# uStar_v1.net
KiCad netlist of a schematic drawn in EAGLE
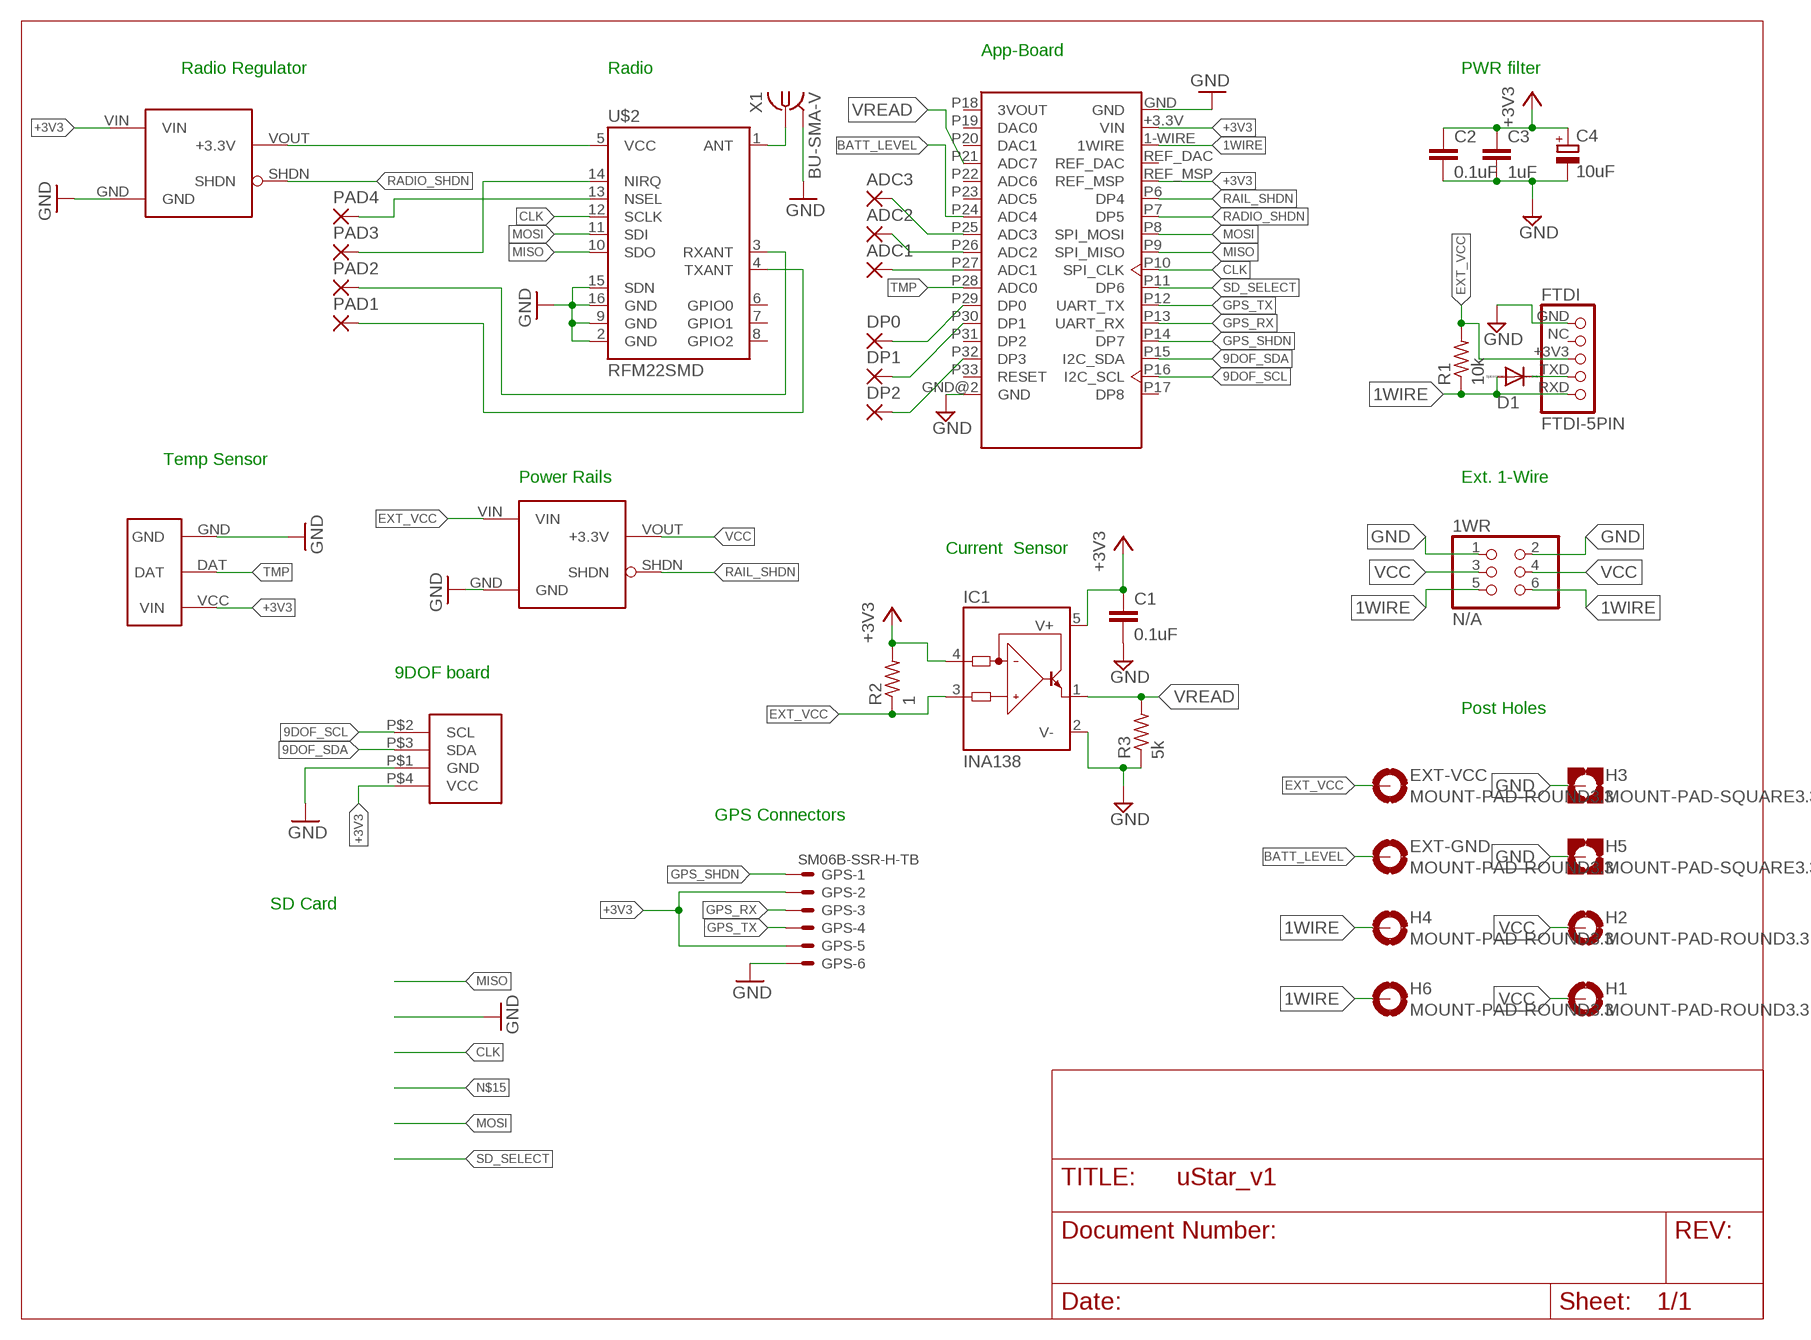
[diagram p0: schematic, sheet 1]

(export (version "E")
  (design (tool "Eeschema 10.0.6"))
  (components
    (comp (ref "1WR")
      (value "N/A")
      (footprint "eagle-import:2X03")
      (libsource (lib "eagle-import") (part "PINHD-2X3"))
    )
    (comp (ref "ADC1")
      (value "1,6/0,9")
      (footprint "eagle-import:1,6_0,9")
      (libsource (lib "eagle-import") (part "1,6/0,9"))
    )
    (comp (ref "ADC2")
      (value "1,6/0,9")
      (footprint "eagle-import:1,6_0,9")
      (libsource (lib "eagle-import") (part "1,6/0,9"))
    )
    (comp (ref "ADC3")
      (value "1,6/0,9")
      (footprint "eagle-import:1,6_0,9")
      (libsource (lib "eagle-import") (part "1,6/0,9"))
    )
    (comp (ref "C1")
      (value "0.1uF")
      (footprint "eagle-import:C0805")
      (libsource (lib "eagle-import") (part "C-EUC0805"))
    )
    (comp (ref "C2")
      (value "0.1uF")
      (footprint "eagle-import:C0603")
      (libsource (lib "eagle-import") (part "C-EUC0603"))
    )
    (comp (ref "C3")
      (value "1uF")
      (footprint "eagle-import:C0603")
      (libsource (lib "eagle-import") (part "C-EUC0603"))
    )
    (comp (ref "C4")
      (value "10uF")
      (footprint "eagle-import:SMC_B")
      (libsource (lib "eagle-import") (part "CPOL-EUSMCB"))
    )
    (comp (ref "D1")
      (value "1N4148DO35-7")
      (footprint "eagle-import:DO35-7")
      (libsource (lib "eagle-import") (part "1N4148DO35-7"))
    )
    (comp (ref "DP0")
      (value "1,6/0,9")
      (footprint "eagle-import:1,6_0,9")
      (libsource (lib "eagle-import") (part "1,6/0,9"))
    )
    (comp (ref "DP1")
      (value "1,6/0,9")
      (footprint "eagle-import:1,6_0,9")
      (libsource (lib "eagle-import") (part "1,6/0,9"))
    )
    (comp (ref "DP2")
      (value "1,6/0,9")
      (footprint "eagle-import:1,6_0,9")
      (libsource (lib "eagle-import") (part "1,6/0,9"))
    )
    (comp (ref "EXT-GND")
      (value "MOUNT-PAD-ROUND3.3")
      (footprint "eagle-import:3,3-PAD")
      (libsource (lib "eagle-import") (part "MOUNT-PAD-ROUND3.3"))
    )
    (comp (ref "EXT-VCC")
      (value "MOUNT-PAD-ROUND3.3")
      (footprint "eagle-import:3,3-PAD")
      (libsource (lib "eagle-import") (part "MOUNT-PAD-ROUND3.3"))
    )
    (comp (ref "FTDI")
      (value "FTDI-5PIN")
      (footprint "eagle-import:1_05X2MM")
      (libsource (lib "eagle-import") (part "FTDI-5PIN"))
    )
    (comp (ref "GPS")
      (value "SM06B-SSR-H-TB")
      (footprint "eagle-import:SM06B-SSR-H-TB")
      (libsource (lib "eagle-import") (part "SM06B-SSR-H-TB"))
    )
    (comp (ref "H1")
      (value "MOUNT-PAD-ROUND3.3")
      (footprint "eagle-import:3,3-PAD")
      (libsource (lib "eagle-import") (part "MOUNT-PAD-ROUND3.3"))
    )
    (comp (ref "H2")
      (value "MOUNT-PAD-ROUND3.3")
      (footprint "eagle-import:3,3-PAD")
      (libsource (lib "eagle-import") (part "MOUNT-PAD-ROUND3.3"))
    )
    (comp (ref "H3")
      (value "MOUNT-PAD-SQUARE3.3")
      (footprint "eagle-import:3,3-PAD-SQUARE")
      (libsource (lib "eagle-import") (part "MOUNT-PAD-SQUARE3.3"))
    )
    (comp (ref "H4")
      (value "MOUNT-PAD-ROUND3.3")
      (footprint "eagle-import:3,3-PAD")
      (libsource (lib "eagle-import") (part "MOUNT-PAD-ROUND3.3"))
    )
    (comp (ref "H5")
      (value "MOUNT-PAD-SQUARE3.3")
      (footprint "eagle-import:3,3-PAD-SQUARE")
      (libsource (lib "eagle-import") (part "MOUNT-PAD-SQUARE3.3"))
    )
    (comp (ref "H6")
      (value "MOUNT-PAD-ROUND3.3")
      (footprint "eagle-import:3,3-PAD")
      (libsource (lib "eagle-import") (part "MOUNT-PAD-ROUND3.3"))
    )
    (comp (ref "IC1")
      (value "INA138")
      (footprint "eagle-import:SOT23-5")
      (fields (field (name "MF") "TEXAS INSTRUMENTS") (field (name "MPN") "INA138NA/250"))
      (libsource (lib "eagle-import") (part "INA138"))
    )
    (comp (ref "PAD1")
      (value "1,6/0,9")
      (footprint "eagle-import:1,6_0,9")
      (libsource (lib "eagle-import") (part "1,6/0,9"))
    )
    (comp (ref "PAD2")
      (value "1,6/0,9")
      (footprint "eagle-import:1,6_0,9")
      (libsource (lib "eagle-import") (part "1,6/0,9"))
    )
    (comp (ref "PAD3")
      (value "1,6/0,9")
      (footprint "eagle-import:1,6_0,9")
      (libsource (lib "eagle-import") (part "1,6/0,9"))
    )
    (comp (ref "PAD4")
      (value "1,6/0,9")
      (footprint "eagle-import:1,6_0,9")
      (libsource (lib "eagle-import") (part "1,6/0,9"))
    )
    (comp (ref "R1")
      (value "10k")
      (footprint "eagle-import:0207_7")
      (libsource (lib "eagle-import") (part "R-US_0207/7"))
    )
    (comp (ref "R2")
      (value "1")
      (footprint "eagle-import:R0603")
      (libsource (lib "eagle-import") (part "R-US_R0603"))
    )
    (comp (ref "R3")
      (value "5k")
      (footprint "eagle-import:R0603")
      (libsource (lib "eagle-import") (part "R-US_R0603"))
    )
    (comp (ref "U$1")
      (value "App-Board 1.2/1.3")
      (footprint "eagle-import:APPCORE_RECEIVER")
      (libsource (lib "eagle-import") (part "APP_CORE"))
    )
    (comp (ref "U$2")
      (value "RFM22SMD")
      (footprint "eagle-import:RFM22-XXX-S2")
      (libsource (lib "eagle-import") (part "RFM22SMD"))
    )
    (comp (ref "U$3")
      (value "S7V8F3_VOLT_REG-3V3_1AHORZ-DOWN")
      (footprint "eagle-import:S7V_DOWN")
      (libsource (lib "eagle-import") (part "S7V8F3_VOLT_REG-3V3_1AHORZ-DOWN"))
    )
    (comp (ref "U$4")
      (value "TMP_EXT")
      (footprint "eagle-import:TMP_EXT")
      (libsource (lib "eagle-import") (part "TMP_EXT"))
    )
    (comp (ref "U$5")
      (value "9DOF")
      (footprint "eagle-import:9DOF")
      (libsource (lib "eagle-import") (part "9DOF"))
    )
    (comp (ref "U$7")
      (value "S7V8F3_VOLT_REG-3V3_1AHORZ-DOWN")
      (footprint "eagle-import:S7V_DOWN")
      (libsource (lib "eagle-import") (part "S7V8F3_VOLT_REG-3V3_1AHORZ-DOWN"))
    )
    (comp (ref "X1")
      (value "BU-SMA-V")
      (footprint "eagle-import:BU-SMA-V")
      (libsource (lib "eagle-import") (part "BU-SMA-V"))
    )
  )
  (nets
    (net (code "1") (name "+3V3") (class "Default")
      (node (ref "C1") (pin "1") (pinfunction "1_1") (pintype "passive"))
      (node (ref "C2") (pin "1") (pinfunction "1_1") (pintype "passive"))
      (node (ref "C3") (pin "1") (pinfunction "1_1") (pintype "passive"))
      (node (ref "C4") (pin "+") (pinfunction "+_+") (pintype "passive"))
      (node (ref "GPS") (pin "2") (pinfunction "S_2") (pintype "passive"))
      (node (ref "GPS") (pin "5") (pinfunction "S_5") (pintype "passive"))
      (node (ref "IC1") (pin "4") (pinfunction "IN-_4") (pintype "input"))
      (node (ref "IC1") (pin "5") (pinfunction "V+_5") (pintype "power_in"))
      (node (ref "R2") (pin "2") (pinfunction "2_2") (pintype "passive"))
      (node (ref "U$1") (pin "+3.3V") (pinfunction "VIN_+3.3V") (pintype "power_in"))
      (node (ref "U$1") (pin "REF_MSP") (pinfunction "REF_MSP_REF_MSP") (pintype "input"))
      (node (ref "U$3") (pin "VIN") (pinfunction "VIN_VIN") (pintype "power_in"))
      (node (ref "U$4") (pin "VCC") (pinfunction "VIN_VCC") (pintype "bidirectional"))
      (node (ref "U$5") (pin "P$4") (pinfunction "VCC_P$4") (pintype "bidirectional"))
    )
    (net (code "2") (name "1WIRE") (class "Default")
      (node (ref "1WR") (pin "5") (pinfunction "5_5") (pintype "passive"))
      (node (ref "1WR") (pin "6") (pinfunction "6_6") (pintype "passive"))
      (node (ref "D1") (pin "A") (pinfunction "A_A") (pintype "passive"))
      (node (ref "FTDI") (pin "RXD") (pinfunction "RXD_RXD") (pintype "input"))
      (node (ref "H4") (pin "B3,3") (pinfunction "MOUNT_B3,3") (pintype "passive"))
      (node (ref "H6") (pin "B3,3") (pinfunction "MOUNT_B3,3") (pintype "passive"))
      (node (ref "R1") (pin "1") (pinfunction "1_1") (pintype "passive"))
      (node (ref "U$1") (pin "1-WIRE") (pinfunction "1WIRE_1-WIRE") (pintype "bidirectional"))
    )
    (net (code "3") (name "9DOF_SCL") (class "Default")
      (node (ref "U$1") (pin "P16") (pinfunction "I2C_SCL_P16") (pintype "bidirectional"))
      (node (ref "U$5") (pin "P$2") (pinfunction "SCL_P$2") (pintype "bidirectional"))
    )
    (net (code "4") (name "9DOF_SDA") (class "Default")
      (node (ref "U$1") (pin "P15") (pinfunction "I2C_SDA_P15") (pintype "bidirectional"))
      (node (ref "U$5") (pin "P$3") (pinfunction "SDA_P$3") (pintype "bidirectional"))
    )
    (net (code "5") (name "BATT_LEVEL") (class "Default")
      (node (ref "EXT-GND") (pin "B3,3") (pinfunction "MOUNT_B3,3") (pintype "passive"))
      (node (ref "U$1") (pin "P24") (pinfunction "ADC4_P24") (pintype "input"))
    )
    (net (code "6") (name "CLK") (class "Default")
      (node (ref "U$1") (pin "P10") (pinfunction "SPI_CLK_P10") (pintype "bidirectional"))
      (node (ref "U$2") (pin "12") (pinfunction "SCLK_12") (pintype "input"))
    )
    (net (code "7") (name "EXT_VCC") (class "Default")
      (node (ref "EXT-VCC") (pin "B3,3") (pinfunction "MOUNT_B3,3") (pintype "passive"))
      (node (ref "FTDI") (pin "+3V3") (pinfunction "+3V3_+3V3") (pintype "power_in"))
      (node (ref "IC1") (pin "3") (pinfunction "IN+_3") (pintype "input"))
      (node (ref "R1") (pin "2") (pinfunction "2_2") (pintype "passive"))
      (node (ref "R2") (pin "1") (pinfunction "1_1") (pintype "passive"))
      (node (ref "U$7") (pin "VIN") (pinfunction "VIN_VIN") (pintype "power_in"))
    )
    (net (code "8") (name "GND") (class "Default")
      (node (ref "1WR") (pin "1") (pinfunction "1_1") (pintype "passive"))
      (node (ref "1WR") (pin "2") (pinfunction "2_2") (pintype "passive"))
      (node (ref "C1") (pin "2") (pinfunction "2_2") (pintype "passive"))
      (node (ref "C2") (pin "2") (pinfunction "2_2") (pintype "passive"))
      (node (ref "C3") (pin "2") (pinfunction "2_2") (pintype "passive"))
      (node (ref "C4") (pin "-") (pinfunction "-_-") (pintype "passive"))
      (node (ref "FTDI") (pin "GND") (pinfunction "GND_GND") (pintype "power_in"))
      (node (ref "GPS") (pin "6") (pinfunction "S_6") (pintype "passive"))
      (node (ref "H3") (pin "B3,3") (pinfunction "MOUNT_B3,3") (pintype "passive"))
      (node (ref "H5") (pin "B3,3") (pinfunction "MOUNT_B3,3") (pintype "passive"))
      (node (ref "IC1") (pin "2") (pinfunction "V-_2") (pintype "power_in"))
      (node (ref "R3") (pin "1") (pinfunction "1_1") (pintype "passive"))
      (node (ref "U$1") (pin "GND") (pinfunction "GND_GND") (pintype "power_in"))
      (node (ref "U$1") (pin "GND@2") (pinfunction "GND_GND@2") (pintype "power_in"))
      (node (ref "U$2") (pin "15") (pinfunction "SDN_15") (pintype "input"))
      (node (ref "U$2") (pin "16") (pinfunction "GND_16") (pintype "power_in"))
      (node (ref "U$2") (pin "2") (pinfunction "GND_2") (pintype "power_in"))
      (node (ref "U$2") (pin "9") (pinfunction "GND_9") (pintype "power_in"))
      (node (ref "U$3") (pin "GND") (pinfunction "GND_GND") (pintype "power_in"))
      (node (ref "U$4") (pin "GND") (pinfunction "GND_GND") (pintype "bidirectional"))
      (node (ref "U$5") (pin "P$1") (pinfunction "GND_P$1") (pintype "bidirectional"))
      (node (ref "U$7") (pin "GND") (pinfunction "GND_GND") (pintype "power_in"))
      (node (ref "X1") (pin "2") (pinfunction "2_2") (pintype "passive"))
      (node (ref "X1") (pin "3") (pinfunction "2_3") (pintype "passive"))
      (node (ref "X1") (pin "4") (pinfunction "2_4") (pintype "passive"))
      (node (ref "X1") (pin "5") (pinfunction "2_5") (pintype "passive"))
    )
    (net (code "9") (name "GPS_RX") (class "Default")
      (node (ref "GPS") (pin "3") (pinfunction "S_3") (pintype "passive"))
      (node (ref "U$1") (pin "P13") (pinfunction "UART_RX_P13") (pintype "input"))
    )
    (net (code "10") (name "GPS_SHDN") (class "Default")
      (node (ref "GPS") (pin "1") (pinfunction "S_1") (pintype "passive"))
      (node (ref "U$1") (pin "P14") (pinfunction "DP7_P14") (pintype "bidirectional"))
    )
    (net (code "11") (name "GPS_TX") (class "Default")
      (node (ref "GPS") (pin "4") (pinfunction "S_4") (pintype "passive"))
      (node (ref "U$1") (pin "P12") (pinfunction "UART_TX_P12") (pintype "output"))
    )
    (net (code "12") (name "MISO") (class "Default")
      (node (ref "U$1") (pin "P9") (pinfunction "SPI_MISO_P9") (pintype "bidirectional"))
      (node (ref "U$2") (pin "10") (pinfunction "SDO_10") (pintype "output"))
    )
    (net (code "13") (name "MOSI") (class "Default")
      (node (ref "U$1") (pin "P8") (pinfunction "SPI_MOSI_P8") (pintype "bidirectional"))
      (node (ref "U$2") (pin "11") (pinfunction "SDI_11") (pintype "input"))
    )
    (net (code "15") (name "Net-(ADC1-P)") (class "Default")
      (node (ref "ADC1") (pin "1") (pinfunction "P_1") (pintype "passive"))
      (node (ref "U$1") (pin "P27") (pinfunction "ADC1_P27") (pintype "input"))
    )
    (net (code "16") (name "Net-(ADC2-P)") (class "Default")
      (node (ref "ADC2") (pin "1") (pinfunction "P_1") (pintype "passive"))
      (node (ref "U$1") (pin "P26") (pinfunction "ADC2_P26") (pintype "input"))
    )
    (net (code "17") (name "Net-(ADC3-P)") (class "Default")
      (node (ref "ADC3") (pin "1") (pinfunction "P_1") (pintype "passive"))
      (node (ref "U$1") (pin "P25") (pinfunction "ADC3_P25") (pintype "input"))
    )
    (net (code "18") (name "Net-(D1-PadC)") (class "Default")
      (node (ref "D1") (pin "C") (pinfunction "C_C") (pintype "passive"))
      (node (ref "FTDI") (pin "TXD") (pinfunction "TXD_TXD") (pintype "output"))
    )
    (net (code "19") (name "Net-(DP0-P)") (class "Default")
      (node (ref "DP0") (pin "1") (pinfunction "P_1") (pintype "passive"))
      (node (ref "U$1") (pin "P29") (pinfunction "DP0_P29") (pintype "bidirectional"))
    )
    (net (code "20") (name "Net-(DP1-P)") (class "Default")
      (node (ref "DP1") (pin "1") (pinfunction "P_1") (pintype "passive"))
      (node (ref "U$1") (pin "P30") (pinfunction "DP1_P30") (pintype "bidirectional"))
    )
    (net (code "21") (name "Net-(DP2-P)") (class "Default")
      (node (ref "DP2") (pin "1") (pinfunction "P_1") (pintype "passive"))
      (node (ref "U$1") (pin "P32") (pinfunction "DP3_P32") (pintype "bidirectional"))
    )
    (net (code "22") (name "Net-(PAD1-P)") (class "Default")
      (node (ref "PAD1") (pin "1") (pinfunction "P_1") (pintype "passive"))
      (node (ref "U$2") (pin "4") (pinfunction "TXANT_4") (pintype "input"))
    )
    (net (code "23") (name "Net-(PAD2-P)") (class "Default")
      (node (ref "PAD2") (pin "1") (pinfunction "P_1") (pintype "passive"))
      (node (ref "U$2") (pin "3") (pinfunction "RXANT_3") (pintype "input"))
    )
    (net (code "24") (name "Net-(PAD3-P)") (class "Default")
      (node (ref "PAD3") (pin "1") (pinfunction "P_1") (pintype "passive"))
      (node (ref "U$2") (pin "14") (pinfunction "NIRQ_14") (pintype "output"))
    )
    (net (code "25") (name "Net-(PAD4-P)") (class "Default")
      (node (ref "PAD4") (pin "1") (pinfunction "P_1") (pintype "passive"))
      (node (ref "U$2") (pin "13") (pinfunction "NSEL_13") (pintype "input"))
    )
    (net (code "26") (name "Net-(U$2-ANT)") (class "Default")
      (node (ref "U$2") (pin "1") (pinfunction "ANT_1") (pintype "bidirectional"))
      (node (ref "X1") (pin "1") (pinfunction "1_1") (pintype "passive"))
    )
    (net (code "27") (name "Net-(U$2-VCC)") (class "Default")
      (node (ref "U$2") (pin "5") (pinfunction "VCC_5") (pintype "bidirectional"))
      (node (ref "U$3") (pin "VOUT") (pinfunction "+3.3V_VOUT") (pintype "output"))
    )
    (net (code "28") (name "RADIO_SHDN") (class "Default")
      (node (ref "U$1") (pin "P7") (pinfunction "DP5_P7") (pintype "bidirectional"))
      (node (ref "U$3") (pin "SHDN") (pinfunction "SHDN_SHDN") (pintype "input"))
    )
    (net (code "29") (name "RAIL_SHDN") (class "Default")
      (node (ref "U$1") (pin "P6") (pinfunction "DP4_P6") (pintype "bidirectional"))
      (node (ref "U$7") (pin "SHDN") (pinfunction "SHDN_SHDN") (pintype "input"))
    )
    (net (code "30") (name "SD_SELECT") (class "Default")
      (node (ref "U$1") (pin "P11") (pinfunction "DP6_P11") (pintype "bidirectional"))
    )
    (net (code "31") (name "TMP") (class "Default")
      (node (ref "U$1") (pin "P28") (pinfunction "ADC0_P28") (pintype "input"))
      (node (ref "U$4") (pin "DAT") (pinfunction "DAT_DAT") (pintype "bidirectional"))
    )
    (net (code "32") (name "VCC") (class "Default")
      (node (ref "1WR") (pin "3") (pinfunction "3_3") (pintype "passive"))
      (node (ref "1WR") (pin "4") (pinfunction "4_4") (pintype "passive"))
      (node (ref "H1") (pin "B3,3") (pinfunction "MOUNT_B3,3") (pintype "passive"))
      (node (ref "H2") (pin "B3,3") (pinfunction "MOUNT_B3,3") (pintype "passive"))
      (node (ref "U$7") (pin "VOUT") (pinfunction "+3.3V_VOUT") (pintype "output"))
    )
    (net (code "33") (name "VREAD") (class "Default")
      (node (ref "IC1") (pin "1") (pinfunction "OUT_1") (pintype "output"))
      (node (ref "R3") (pin "2") (pinfunction "2_2") (pintype "passive"))
      (node (ref "U$1") (pin "P21") (pinfunction "ADC7_P21") (pintype "input"))
    )
    (net (code "34") (name "unconnected-(FTDI-PadNC)") (class "Default")
      (node (ref "FTDI") (pin "NC") (pinfunction "NC_NC") (pintype "no_connect"))
    )
    (net (code "35") (name "unconnected-(U$1-3VOUT-PadP18)") (class "Default")
      (node (ref "U$1") (pin "P18") (pinfunction "3VOUT_P18") (pintype "output"))
    )
    (net (code "36") (name "unconnected-(U$1-ADC5-PadP23)") (class "Default")
      (node (ref "U$1") (pin "P23") (pinfunction "ADC5_P23") (pintype "input"))
    )
    (net (code "37") (name "unconnected-(U$1-ADC6-PadP22)") (class "Default")
      (node (ref "U$1") (pin "P22") (pinfunction "ADC6_P22") (pintype "input"))
    )
    (net (code "38") (name "unconnected-(U$1-DAC0-PadP19)") (class "Default")
      (node (ref "U$1") (pin "P19") (pinfunction "DAC0_P19") (pintype "bidirectional"))
    )
    (net (code "39") (name "unconnected-(U$1-DAC1-PadP20)") (class "Default")
      (node (ref "U$1") (pin "P20") (pinfunction "DAC1_P20") (pintype "bidirectional"))
    )
    (net (code "40") (name "unconnected-(U$1-DP2-PadP31)") (class "Default")
      (node (ref "U$1") (pin "P31") (pinfunction "DP2_P31") (pintype "bidirectional"))
    )
    (net (code "41") (name "unconnected-(U$1-DP8-PadP17)") (class "Default")
      (node (ref "U$1") (pin "P17") (pinfunction "DP8_P17") (pintype "bidirectional"))
    )
    (net (code "42") (name "unconnected-(U$1-PadREF_DAC)") (class "Default")
      (node (ref "U$1") (pin "REF_DAC") (pinfunction "REF_DAC_REF_DAC") (pintype "input"))
    )
    (net (code "43") (name "unconnected-(U$1-RESET-PadP33)") (class "Default")
      (node (ref "U$1") (pin "P33") (pinfunction "RESET_P33") (pintype "bidirectional"))
    )
    (net (code "44") (name "unconnected-(U$2-GPIO0-Pad6)") (class "Default")
      (node (ref "U$2") (pin "6") (pinfunction "GPIO0_6") (pintype "bidirectional"))
    )
    (net (code "45") (name "unconnected-(U$2-GPIO1-Pad7)") (class "Default")
      (node (ref "U$2") (pin "7") (pinfunction "GPIO1_7") (pintype "bidirectional"))
    )
    (net (code "46") (name "unconnected-(U$2-GPIO2-Pad8)") (class "Default")
      (node (ref "U$2") (pin "8") (pinfunction "GPIO2_8") (pintype "bidirectional"))
    )
  )
)
